# io.net
KiCad netlist of a schematic drawn in EAGLE
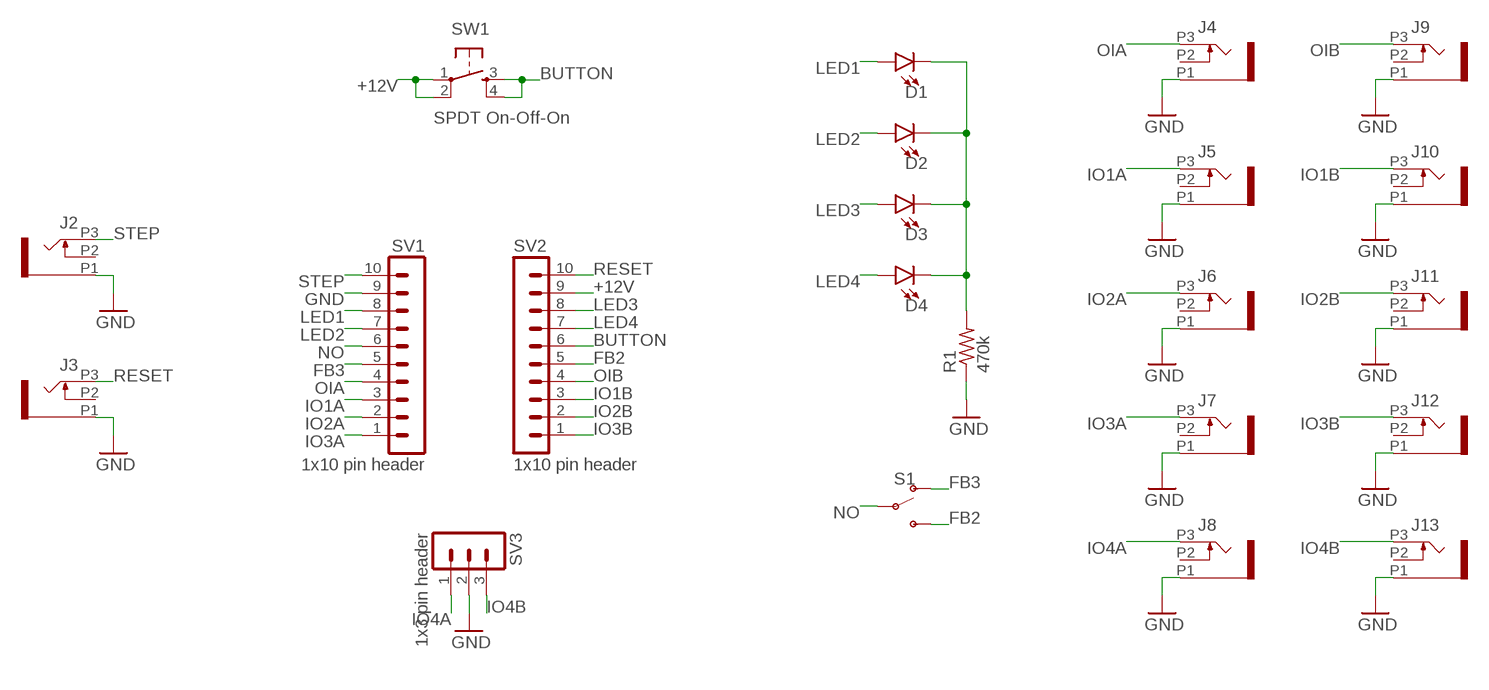
[diagram p0: schematic, sheet 1]

(export (version "E")
  (design (tool "Eeschema 10.0.6"))
  (components
    (comp (ref "D1")
      (value "LED3MM")
      (footprint "eagle-import:LED_3MM")
      (libsource (lib "eagle-import") (part "LED3MM"))
    )
    (comp (ref "D2")
      (value "LED3MM")
      (footprint "eagle-import:LED_3MM")
      (libsource (lib "eagle-import") (part "LED3MM"))
    )
    (comp (ref "D3")
      (value "LED3MM")
      (footprint "eagle-import:LED_3MM")
      (libsource (lib "eagle-import") (part "LED3MM"))
    )
    (comp (ref "D4")
      (value "LED3MM")
      (footprint "eagle-import:LED_3MM")
      (libsource (lib "eagle-import") (part "LED3MM"))
    )
    (comp (ref "J2")
      (value "PJ301_THONKICONN6")
      (footprint "eagle-import:WQP_PJ_301M6")
      (libsource (lib "eagle-import") (part "PJ301_THONKICONN6"))
    )
    (comp (ref "J3")
      (value "PJ301_THONKICONN6")
      (footprint "eagle-import:WQP_PJ_301M6")
      (libsource (lib "eagle-import") (part "PJ301_THONKICONN6"))
    )
    (comp (ref "J4")
      (value "PJ301_THONKICONN6")
      (footprint "eagle-import:WQP_PJ_301M6")
      (libsource (lib "eagle-import") (part "PJ301_THONKICONN6"))
    )
    (comp (ref "J5")
      (value "PJ301_THONKICONN6")
      (footprint "eagle-import:WQP_PJ_301M6")
      (libsource (lib "eagle-import") (part "PJ301_THONKICONN6"))
    )
    (comp (ref "J6")
      (value "PJ301_THONKICONN6")
      (footprint "eagle-import:WQP_PJ_301M6")
      (libsource (lib "eagle-import") (part "PJ301_THONKICONN6"))
    )
    (comp (ref "J7")
      (value "PJ301_THONKICONN6")
      (footprint "eagle-import:WQP_PJ_301M6")
      (libsource (lib "eagle-import") (part "PJ301_THONKICONN6"))
    )
    (comp (ref "J8")
      (value "PJ301_THONKICONN6")
      (footprint "eagle-import:WQP_PJ_301M6")
      (libsource (lib "eagle-import") (part "PJ301_THONKICONN6"))
    )
    (comp (ref "J9")
      (value "PJ301_THONKICONN6")
      (footprint "eagle-import:WQP_PJ_301M6")
      (libsource (lib "eagle-import") (part "PJ301_THONKICONN6"))
    )
    (comp (ref "J10")
      (value "PJ301_THONKICONN6")
      (footprint "eagle-import:WQP_PJ_301M6")
      (libsource (lib "eagle-import") (part "PJ301_THONKICONN6"))
    )
    (comp (ref "J11")
      (value "PJ301_THONKICONN6")
      (footprint "eagle-import:WQP_PJ_301M6")
      (libsource (lib "eagle-import") (part "PJ301_THONKICONN6"))
    )
    (comp (ref "J12")
      (value "PJ301_THONKICONN6")
      (footprint "eagle-import:WQP_PJ_301M6")
      (libsource (lib "eagle-import") (part "PJ301_THONKICONN6"))
    )
    (comp (ref "J13")
      (value "PJ301_THONKICONN6")
      (footprint "eagle-import:WQP_PJ_301M6")
      (libsource (lib "eagle-import") (part "PJ301_THONKICONN6"))
    )
    (comp (ref "R1")
      (value "470k")
      (footprint "eagle-import:R0603")
      (libsource (lib "eagle-import") (part "R-US_R0603"))
    )
    (comp (ref "S1")
      (value "SWITCH-SPDT-PTH-11.6X4.0MM-SHORT_LEADS")
      (footprint "eagle-import:SWITCH_SPDT_PTH_11.6X4.0MM")
      (libsource (lib "eagle-import") (part "SWITCH-SPDT-PTH-11.6X4.0MM-SHORT_LEADS"))
    )
    (comp (ref "SV1")
      (value "1x10 pin header")
      (footprint "eagle-import:MA10-1")
      (libsource (lib "eagle-import") (part "MA10-1"))
    )
    (comp (ref "SV2")
      (value "1x10 pin header")
      (footprint "eagle-import:MA10-1")
      (libsource (lib "eagle-import") (part "MA10-1"))
    )
    (comp (ref "SV3")
      (value "1x3 pin header")
      (footprint "eagle-import:MA03-1")
      (libsource (lib "eagle-import") (part "MA03-1"))
    )
    (comp (ref "SW1")
      (value "SPDT On-Off-On")
      (footprint "eagle-import:TACTILE-PTH")
      (libsource (lib "eagle-import") (part "TAC_SWITCHPTH"))
    )
  )
  (nets
    (net (code "1") (name "/+12V") (class "Default")
      (node (ref "SV2") (pin "9") (pinfunction "9_9") (pintype "passive"))
      (node (ref "SW1") (pin "1") (pinfunction "1_1") (pintype "passive"))
      (node (ref "SW1") (pin "2") (pinfunction "2_2") (pintype "passive"))
    )
    (net (code "2") (name "/BUTTON") (class "Default")
      (node (ref "SV2") (pin "6") (pinfunction "6_6") (pintype "passive"))
      (node (ref "SW1") (pin "3") (pinfunction "3_3") (pintype "passive"))
      (node (ref "SW1") (pin "4") (pinfunction "4_4") (pintype "passive"))
    )
    (net (code "3") (name "/FB2") (class "Default")
      (node (ref "S1") (pin "3") (pinfunction "S_3") (pintype "passive"))
      (node (ref "SV2") (pin "5") (pinfunction "5_5") (pintype "passive"))
    )
    (net (code "4") (name "/FB3") (class "Default")
      (node (ref "S1") (pin "1") (pinfunction "O_1") (pintype "passive"))
      (node (ref "SV1") (pin "5") (pinfunction "5_5") (pintype "passive"))
    )
    (net (code "5") (name "/IO1A") (class "Default")
      (node (ref "J5") (pin "P3") (pinfunction "3_P3") (pintype "passive"))
      (node (ref "SV1") (pin "3") (pinfunction "3_3") (pintype "passive"))
    )
    (net (code "6") (name "/IO1B") (class "Default")
      (node (ref "J10") (pin "P3") (pinfunction "3_P3") (pintype "passive"))
      (node (ref "SV2") (pin "3") (pinfunction "3_3") (pintype "passive"))
    )
    (net (code "7") (name "/IO2A") (class "Default")
      (node (ref "J6") (pin "P3") (pinfunction "3_P3") (pintype "passive"))
      (node (ref "SV1") (pin "2") (pinfunction "2_2") (pintype "passive"))
    )
    (net (code "8") (name "/IO2B") (class "Default")
      (node (ref "J11") (pin "P3") (pinfunction "3_P3") (pintype "passive"))
      (node (ref "SV2") (pin "2") (pinfunction "2_2") (pintype "passive"))
    )
    (net (code "9") (name "/IO3A") (class "Default")
      (node (ref "J7") (pin "P3") (pinfunction "3_P3") (pintype "passive"))
      (node (ref "SV1") (pin "1") (pinfunction "1_1") (pintype "passive"))
    )
    (net (code "10") (name "/IO3B") (class "Default")
      (node (ref "J12") (pin "P3") (pinfunction "3_P3") (pintype "passive"))
      (node (ref "SV2") (pin "1") (pinfunction "1_1") (pintype "passive"))
    )
    (net (code "11") (name "/IO4A") (class "Default")
      (node (ref "J8") (pin "P3") (pinfunction "3_P3") (pintype "passive"))
      (node (ref "SV3") (pin "1") (pinfunction "1_1") (pintype "passive"))
    )
    (net (code "12") (name "/IO4B") (class "Default")
      (node (ref "J13") (pin "P3") (pinfunction "3_P3") (pintype "passive"))
      (node (ref "SV3") (pin "3") (pinfunction "3_3") (pintype "passive"))
    )
    (net (code "13") (name "/LED1") (class "Default")
      (node (ref "D1") (pin "A") (pinfunction "A_A") (pintype "passive"))
      (node (ref "SV1") (pin "8") (pinfunction "8_8") (pintype "passive"))
    )
    (net (code "14") (name "/LED2") (class "Default")
      (node (ref "D2") (pin "A") (pinfunction "A_A") (pintype "passive"))
      (node (ref "SV1") (pin "7") (pinfunction "7_7") (pintype "passive"))
    )
    (net (code "15") (name "/LED3") (class "Default")
      (node (ref "D3") (pin "A") (pinfunction "A_A") (pintype "passive"))
      (node (ref "SV2") (pin "8") (pinfunction "8_8") (pintype "passive"))
    )
    (net (code "16") (name "/LED4") (class "Default")
      (node (ref "D4") (pin "A") (pinfunction "A_A") (pintype "passive"))
      (node (ref "SV2") (pin "7") (pinfunction "7_7") (pintype "passive"))
    )
    (net (code "17") (name "/NO") (class "Default")
      (node (ref "S1") (pin "2") (pinfunction "P_2") (pintype "passive"))
      (node (ref "SV1") (pin "6") (pinfunction "6_6") (pintype "passive"))
    )
    (net (code "18") (name "/OIA") (class "Default")
      (node (ref "J4") (pin "P3") (pinfunction "3_P3") (pintype "passive"))
      (node (ref "SV1") (pin "4") (pinfunction "4_4") (pintype "passive"))
    )
    (net (code "19") (name "/OIB") (class "Default")
      (node (ref "J9") (pin "P3") (pinfunction "3_P3") (pintype "passive"))
      (node (ref "SV2") (pin "4") (pinfunction "4_4") (pintype "passive"))
    )
    (net (code "20") (name "/RESET") (class "Default")
      (node (ref "J3") (pin "P3") (pinfunction "3_P3") (pintype "passive"))
      (node (ref "SV2") (pin "10") (pinfunction "10_10") (pintype "passive"))
    )
    (net (code "21") (name "/STEP") (class "Default")
      (node (ref "J2") (pin "P3") (pinfunction "3_P3") (pintype "passive"))
      (node (ref "SV1") (pin "10") (pinfunction "10_10") (pintype "passive"))
    )
    (net (code "22") (name "GND") (class "Default")
      (node (ref "J10") (pin "P1") (pinfunction "1_P1") (pintype "passive"))
      (node (ref "J11") (pin "P1") (pinfunction "1_P1") (pintype "passive"))
      (node (ref "J12") (pin "P1") (pinfunction "1_P1") (pintype "passive"))
      (node (ref "J13") (pin "P1") (pinfunction "1_P1") (pintype "passive"))
      (node (ref "J2") (pin "P1") (pinfunction "1_P1") (pintype "passive"))
      (node (ref "J3") (pin "P1") (pinfunction "1_P1") (pintype "passive"))
      (node (ref "J4") (pin "P1") (pinfunction "1_P1") (pintype "passive"))
      (node (ref "J5") (pin "P1") (pinfunction "1_P1") (pintype "passive"))
      (node (ref "J6") (pin "P1") (pinfunction "1_P1") (pintype "passive"))
      (node (ref "J7") (pin "P1") (pinfunction "1_P1") (pintype "passive"))
      (node (ref "J8") (pin "P1") (pinfunction "1_P1") (pintype "passive"))
      (node (ref "J9") (pin "P1") (pinfunction "1_P1") (pintype "passive"))
      (node (ref "R1") (pin "1") (pinfunction "1_1") (pintype "passive"))
      (node (ref "SV1") (pin "9") (pinfunction "9_9") (pintype "passive"))
      (node (ref "SV3") (pin "2") (pinfunction "2_2") (pintype "passive"))
    )
    (net (code "23") (name "Net-(D1-C)") (class "Default")
      (node (ref "D1") (pin "K") (pinfunction "C_K") (pintype "passive"))
      (node (ref "D2") (pin "K") (pinfunction "C_K") (pintype "passive"))
      (node (ref "D3") (pin "K") (pinfunction "C_K") (pintype "passive"))
      (node (ref "D4") (pin "K") (pinfunction "C_K") (pintype "passive"))
      (node (ref "R1") (pin "2") (pinfunction "2_2") (pintype "passive"))
    )
    (net (code "24") (name "unconnected-(J2-2-PadP2)") (class "Default")
      (node (ref "J2") (pin "P2") (pinfunction "2_P2") (pintype "passive"))
    )
    (net (code "25") (name "unconnected-(J3-2-PadP2)") (class "Default")
      (node (ref "J3") (pin "P2") (pinfunction "2_P2") (pintype "passive"))
    )
    (net (code "26") (name "unconnected-(J4-2-PadP2)") (class "Default")
      (node (ref "J4") (pin "P2") (pinfunction "2_P2") (pintype "passive"))
    )
    (net (code "27") (name "unconnected-(J5-2-PadP2)") (class "Default")
      (node (ref "J5") (pin "P2") (pinfunction "2_P2") (pintype "passive"))
    )
    (net (code "28") (name "unconnected-(J6-2-PadP2)") (class "Default")
      (node (ref "J6") (pin "P2") (pinfunction "2_P2") (pintype "passive"))
    )
    (net (code "29") (name "unconnected-(J7-2-PadP2)") (class "Default")
      (node (ref "J7") (pin "P2") (pinfunction "2_P2") (pintype "passive"))
    )
    (net (code "30") (name "unconnected-(J8-2-PadP2)") (class "Default")
      (node (ref "J8") (pin "P2") (pinfunction "2_P2") (pintype "passive"))
    )
    (net (code "31") (name "unconnected-(J9-2-PadP2)") (class "Default")
      (node (ref "J9") (pin "P2") (pinfunction "2_P2") (pintype "passive"))
    )
    (net (code "32") (name "unconnected-(J10-2-PadP2)") (class "Default")
      (node (ref "J10") (pin "P2") (pinfunction "2_P2") (pintype "passive"))
    )
    (net (code "33") (name "unconnected-(J11-2-PadP2)") (class "Default")
      (node (ref "J11") (pin "P2") (pinfunction "2_P2") (pintype "passive"))
    )
    (net (code "34") (name "unconnected-(J12-2-PadP2)") (class "Default")
      (node (ref "J12") (pin "P2") (pinfunction "2_P2") (pintype "passive"))
    )
    (net (code "35") (name "unconnected-(J13-2-PadP2)") (class "Default")
      (node (ref "J13") (pin "P2") (pinfunction "2_P2") (pintype "passive"))
    )
  )
)
